# Sheet1.net
KiCad netlist of a schematic drawn in Altium Designer
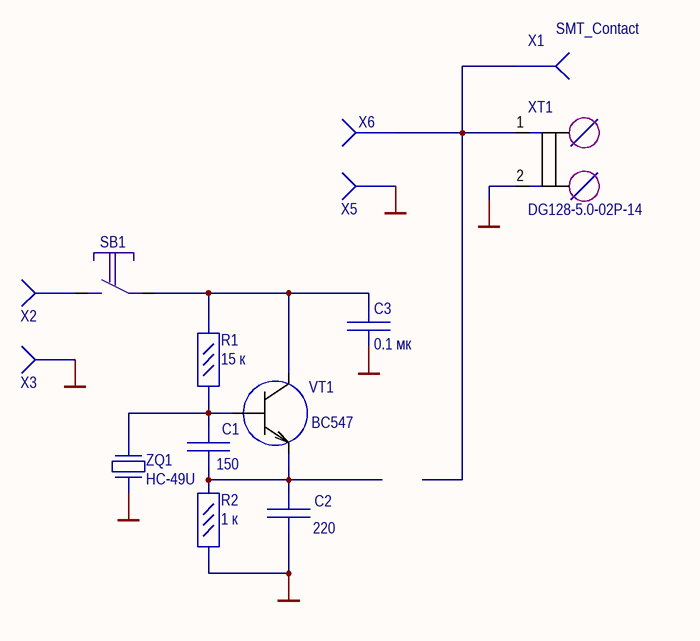
[diagram p0: Sheet1.SchDoc]

(export (version "E")
  (design (tool "Eeschema 10.0.6"))
  (components
    (comp (ref "C1") (value "150") (footprint "К10-17Б") (libsource (lib "1. Passive") (part "C_К10-17Б")))
    (comp (ref "C2") (value "220") (footprint "К10-17Б") (libsource (lib "1. Passive") (part "C_К10-17Б")))
    (comp (ref "C3") (value "0.1 мк") (footprint "К10-17Б") (libsource (lib "1. Passive") (part "C_К10-17Б")))
    (comp (ref "R1") (value "15 к") (footprint "С1-4") (libsource (lib "1. Passive") (part "R_C1-4")))
    (comp (ref "R2") (value "1 к") (footprint "С1-4") (libsource (lib "1. Passive") (part "R_C1-4")))
    (comp (ref "SB1")
      (value "KLS7-TS6601")
      (footprint "KLS7-TS6601")
      (libsource (lib "9.Commutation") (part "KLS7-TS6601"))
    )
    (comp (ref "VT1") (value "BC547") (footprint "КТ-26") (libsource (lib "4. Transistors") (part "BC547")))
    (comp (ref "X1")
      (value "SMT_Contact")
      (footprint "SMT_CONTACT_TYPE_3")
      (libsource (lib "7. Connectors") (part "SMT_Contact"))
    )
    (comp (ref "X2")
      (value "SMT_Contact")
      (footprint "SMT_CONTACT_TYPE_1")
      (libsource (lib "7. Connectors") (part "SMT_Contact"))
    )
    (comp (ref "X3")
      (value "SMT_Contact")
      (footprint "SMT_CONTACT_TYPE_1")
      (libsource (lib "7. Connectors") (part "SMT_Contact"))
    )
    (comp (ref "X5")
      (value "SMT_Contact")
      (footprint "SMT_CONTACT_TYPE_1")
      (libsource (lib "7. Connectors") (part "SMT_Contact"))
    )
    (comp (ref "X6")
      (value "SMT_Contact")
      (footprint "SMT_CONTACT_TYPE_1")
      (libsource (lib "7. Connectors") (part "SMT_Contact"))
    )
    (comp (ref "XT1")
      (value "DG128-5.0-02P-14")
      (footprint "DG128-5.0-02P-14")
      (libsource (lib "7. Connectors") (part "DG128-5.0-02P-14"))
    )
    (comp (ref "ZQ1") (value "HC-49U") (footprint "HC-49U") (libsource (lib "5. Resonarors") (part "HC-49U")))
  )
  (nets
    (net (code "1") (name "GND") (class "Default")
      (node (ref "C2") (pin "2") (pinfunction "2_2") (pintype "passive"))
      (node (ref "C3") (pin "1") (pinfunction "1_1") (pintype "passive"))
      (node (ref "R2") (pin "1") (pinfunction "1_1") (pintype "passive"))
      (node (ref "X3") (pin "1") (pinfunction "1_1") (pintype "passive"))
      (node (ref "X5") (pin "1") (pinfunction "1_1") (pintype "passive"))
      (node (ref "XT1") (pin "2") (pintype "passive"))
      (node (ref "ZQ1") (pin "2") (pinfunction "2_2") (pintype "passive"))
    )
    (net (code "2") (name "Net-(SB1-Pad1)") (class "Default")
      (node (ref "SB1") (pin "1") (pinfunction "1_1") (pintype "passive"))
      (node (ref "X2") (pin "1") (pinfunction "1_1") (pintype "passive"))
    )
    (net (code "3") (name "Net-(VT1-B)") (class "Default")
      (node (ref "C1") (pin "1") (pinfunction "1_1") (pintype "passive"))
      (node (ref "R1") (pin "1") (pinfunction "1_1") (pintype "passive"))
      (node (ref "VT1") (pin "2") (pinfunction "B_2") (pintype "passive"))
      (node (ref "ZQ1") (pin "1") (pinfunction "1_1") (pintype "passive"))
    )
    (net (code "4") (name "Net-(VT1-C)") (class "Default")
      (node (ref "C3") (pin "2") (pinfunction "2_2") (pintype "passive"))
      (node (ref "R1") (pin "2") (pinfunction "2_2") (pintype "passive"))
      (node (ref "SB1") (pin "2") (pinfunction "2_2") (pintype "passive"))
      (node (ref "VT1") (pin "1") (pinfunction "C_1") (pintype "passive"))
    )
    (net (code "5") (name "Net-(VT1-E)") (class "Default")
      (node (ref "C1") (pin "2") (pinfunction "2_2") (pintype "passive"))
      (node (ref "C2") (pin "1") (pinfunction "1_1") (pintype "passive"))
      (node (ref "R2") (pin "2") (pinfunction "2_2") (pintype "passive"))
      (node (ref "VT1") (pin "3") (pinfunction "E_3") (pintype "passive"))
    )
    (net (code "6") (name "Net-(X1-Pad1)") (class "Default")
      (node (ref "X1") (pin "1") (pinfunction "1_1") (pintype "passive"))
      (node (ref "X6") (pin "1") (pinfunction "1_1") (pintype "passive"))
      (node (ref "XT1") (pin "1") (pintype "passive"))
    )
  )
)
